# Acondicionamiento_Presion.net
KiCad netlist of a schematic drawn in Altium Designer
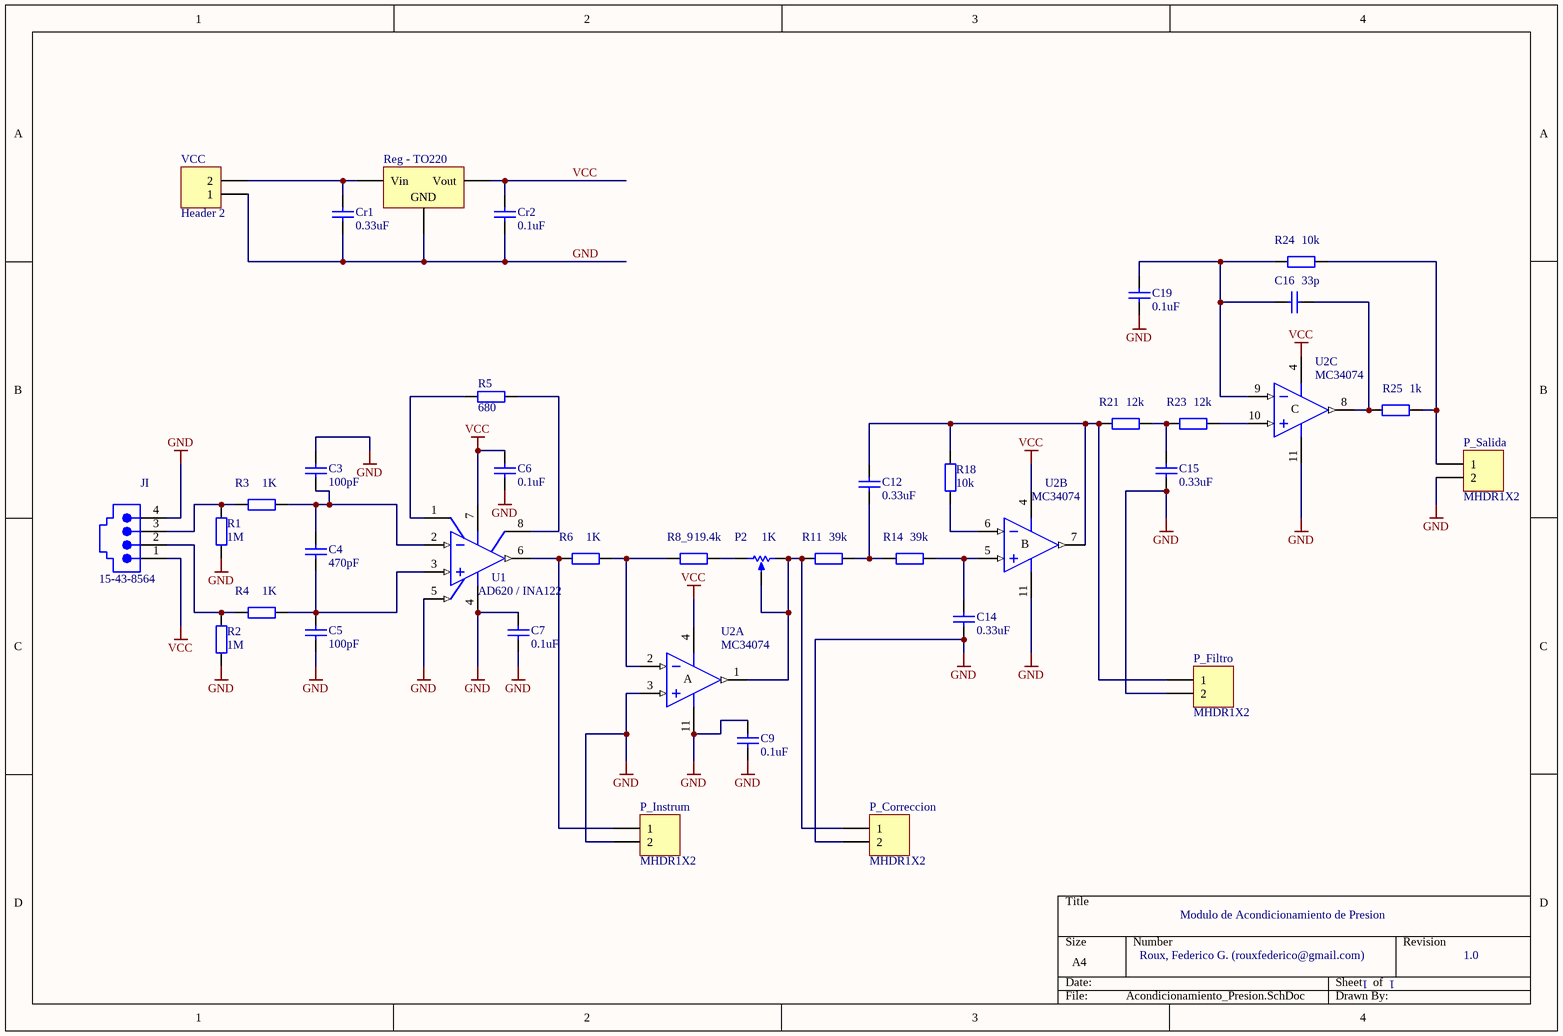
[diagram p0: Acondicionamiento_Presion.SchDoc]

(export (version "E")
  (design (tool "Eeschema 10.0.6"))
  (components
    (comp (ref "C3")
      (value "100pF")
      (footprint "AXIAL-0.3")
      (description "Capacitor")
      (fields (field (name "Comment") "Cap") (field (name "PUBLISHER") "Altium Limited"))
      (libsource (lib "Miscellaneous Devices") (part "Cap"))
    )
    (comp (ref "C4")
      (value "470pF")
      (footprint "AXIAL-0.3")
      (description "Capacitor")
      (fields (field (name "Comment") "Cap") (field (name "PUBLISHER") "Altium Limited"))
      (libsource (lib "Miscellaneous Devices") (part "Cap"))
    )
    (comp (ref "C5")
      (value "100pF")
      (footprint "AXIAL-0.3")
      (description "Capacitor")
      (fields (field (name "Comment") "Cap") (field (name "PUBLISHER") "Altium Limited"))
      (libsource (lib "Miscellaneous Devices") (part "Cap"))
    )
    (comp (ref "C6")
      (value "0.1uF")
      (footprint "AXIAL-0.3")
      (description "Capacitor")
      (fields (field (name "Comment") "Cap") (field (name "PUBLISHER") "Altium Limited"))
      (libsource (lib "Miscellaneous Devices") (part "Cap"))
    )
    (comp (ref "C7")
      (value "0.1uF")
      (footprint "AXIAL-0.3")
      (description "Capacitor")
      (fields (field (name "Comment") "Cap") (field (name "PUBLISHER") "Altium Limited"))
      (libsource (lib "Miscellaneous Devices") (part "Cap"))
    )
    (comp (ref "C9")
      (value "0.1uF")
      (footprint "AXIAL-0.3")
      (description "Capacitor")
      (fields (field (name "Comment") "Cap") (field (name "PUBLISHER") "Altium Limited"))
      (libsource (lib "Miscellaneous Devices") (part "Cap"))
    )
    (comp (ref "C12")
      (value "0.33uF")
      (footprint "AXIAL-0.3")
      (description "Capacitor")
      (fields (field (name "Comment") "Cap") (field (name "PUBLISHER") "Altium Limited"))
      (libsource (lib "Miscellaneous Devices") (part "Cap"))
    )
    (comp (ref "C14")
      (value "0.33uF")
      (footprint "AXIAL-0.3")
      (description "Capacitor")
      (fields (field (name "Comment") "Cap") (field (name "PUBLISHER") "Altium Limited"))
      (libsource (lib "Miscellaneous Devices") (part "Cap"))
    )
    (comp (ref "C15")
      (value "0.33uF")
      (footprint "AXIAL-0.3")
      (description "Capacitor")
      (fields (field (name "Comment") "Cap") (field (name "PUBLISHER") "Altium Limited"))
      (libsource (lib "Miscellaneous Devices") (part "Cap"))
    )
    (comp (ref "C16")
      (value "33p")
      (footprint "AXIAL-0.3")
      (description "Capacitor")
      (fields (field (name "Comment") "Cap") (field (name "PUBLISHER") "Altium Limited"))
      (libsource (lib "Miscellaneous Devices") (part "Cap"))
    )
    (comp (ref "C19")
      (value "0.1uF")
      (footprint "AXIAL-0.3")
      (description "Capacitor")
      (fields (field (name "Comment") "Cap") (field (name "PUBLISHER") "Altium Limited"))
      (libsource (lib "Miscellaneous Devices") (part "Cap"))
    )
    (comp (ref "Cr1")
      (value "0.33uF")
      (footprint "AXIAL-0.3")
      (description "Capacitor")
      (fields (field (name "Comment") "Cap") (field (name "PUBLISHER") "Altium Limited"))
      (libsource (lib "Miscellaneous Devices") (part "Cap"))
    )
    (comp (ref "Cr2")
      (value "0.1uF")
      (footprint "AXIAL-0.3")
      (description "Capacitor")
      (fields (field (name "Comment") "Cap") (field (name "PUBLISHER") "Altium Limited"))
      (libsource (lib "Miscellaneous Devices") (part "Cap"))
    )
    (comp (ref "JI")
      (value "15-43-8564")
      (footprint "15-43-8564")
      (description "Right Angle, Standard Profile, Unshielded PCB Jack")
      (fields (field (name "PUBLISHER") "Altium Limited"))
      (libsource (lib "Molex Modular Jack Right Angle") (part "15-43-8564"))
    )
    (comp (ref "P2")
      (value "1K")
      (footprint "VR5")
      (description "Potentiometer")
      (fields (field (name "Comment") "RPot") (field (name "PUBLISHER") "Altium Limited"))
      (libsource (lib "Miscellaneous Devices") (part "RPot"))
    )
    (comp (ref "P_Correccion")
      (value "MHDR1X2")
      (footprint "MHDR1X2")
      (description "Header, 2-Pin")
      (fields (field (name "PUBLISHER") "Altium Limited"))
      (libsource (lib "Miscellaneous Connectors") (part "MHDR1X2"))
    )
    (comp (ref "P_Filtro")
      (value "MHDR1X2")
      (footprint "MHDR1X2")
      (description "Header, 2-Pin")
      (fields (field (name "PUBLISHER") "Altium Limited"))
      (libsource (lib "Miscellaneous Connectors") (part "MHDR1X2"))
    )
    (comp (ref "P_Instrum")
      (value "MHDR1X2")
      (footprint "MHDR1X2")
      (description "Header, 2-Pin")
      (fields (field (name "PUBLISHER") "Altium Limited"))
      (libsource (lib "Miscellaneous Connectors") (part "MHDR1X2"))
    )
    (comp (ref "P_Salida")
      (value "MHDR1X2")
      (footprint "MHDR1X2")
      (description "Header, 2-Pin")
      (fields (field (name "PUBLISHER") "Altium Limited"))
      (libsource (lib "Miscellaneous Connectors") (part "MHDR1X2"))
    )
    (comp (ref "R1")
      (value "1M")
      (footprint "AXIAL-0.3")
      (description "Resistor")
      (fields (field (name "Comment") "Res2") (field (name "PUBLISHER") "Altium Limited"))
      (libsource (lib "") (part "Res2_2"))
    )
    (comp (ref "R2")
      (value "1M")
      (footprint "AXIAL-0.3")
      (description "Resistor")
      (fields (field (name "Comment") "Res2") (field (name "PUBLISHER") "Altium Limited"))
      (libsource (lib "") (part "Res2_2"))
    )
    (comp (ref "R3")
      (value "1K")
      (footprint "AXIAL-0.3")
      (description "Resistor")
      (fields (field (name "Comment") "Res2") (field (name "PUBLISHER") "Altium Limited"))
      (libsource (lib "") (part "Res2_1"))
    )
    (comp (ref "R4")
      (value "1K")
      (footprint "AXIAL-0.3")
      (description "Resistor")
      (fields (field (name "Comment") "Res2") (field (name "PUBLISHER") "Altium Limited"))
      (libsource (lib "") (part "Res2_1"))
    )
    (comp (ref "R5")
      (value "680")
      (footprint "AXIAL-0.3")
      (description "Resistor")
      (fields (field (name "Comment") "Res2") (field (name "PUBLISHER") "Altium Limited"))
      (libsource (lib "Miscellaneous Devices") (part "Res2"))
    )
    (comp (ref "R6")
      (value "1K")
      (footprint "AXIAL-0.3")
      (description "Resistor")
      (fields (field (name "Comment") "Res2") (field (name "PUBLISHER") "Altium Limited"))
      (libsource (lib "") (part "Res2_1"))
    )
    (comp (ref "R8_9")
      (value "19.4k")
      (footprint "AXIAL-0.3")
      (description "Resistor")
      (fields (field (name "Comment") "Res2") (field (name "PUBLISHER") "Altium Limited"))
      (libsource (lib "") (part "Res2_1"))
    )
    (comp (ref "R11")
      (value "39k")
      (footprint "AXIAL-0.3")
      (description "Resistor")
      (fields (field (name "Comment") "Res2") (field (name "PUBLISHER") "Altium Limited"))
      (libsource (lib "") (part "Res2_1"))
    )
    (comp (ref "R14")
      (value "39k")
      (footprint "AXIAL-0.3")
      (description "Resistor")
      (fields (field (name "Comment") "Res2") (field (name "PUBLISHER") "Altium Limited"))
      (libsource (lib "") (part "Res2_1"))
    )
    (comp (ref "R18")
      (value "10k")
      (footprint "AXIAL-0.3")
      (description "Resistor")
      (fields (field (name "Comment") "Res2") (field (name "PUBLISHER") "Altium Limited"))
      (libsource (lib "") (part "Res2_2"))
    )
    (comp (ref "R21")
      (value "12k")
      (footprint "AXIAL-0.3")
      (description "Resistor")
      (fields (field (name "Comment") "Res2") (field (name "PUBLISHER") "Altium Limited"))
      (libsource (lib "") (part "Res2_1"))
    )
    (comp (ref "R23")
      (value "12k")
      (footprint "AXIAL-0.3")
      (description "Resistor")
      (fields (field (name "Comment") "Res2") (field (name "PUBLISHER") "Altium Limited"))
      (libsource (lib "") (part "Res2_1"))
    )
    (comp (ref "R24")
      (value "10k")
      (footprint "AXIAL-0.3")
      (description "Resistor")
      (fields (field (name "Comment") "Res2") (field (name "PUBLISHER") "Altium Limited"))
      (libsource (lib "") (part "Res2_1"))
    )
    (comp (ref "R25")
      (value "1k")
      (footprint "AXIAL-0.3")
      (description "Resistor")
      (fields (field (name "Comment") "Res2") (field (name "PUBLISHER") "Altium Limited"))
      (libsource (lib "") (part "Res2_1"))
    )
    (comp (ref "Reg - TO220")
      (value "Volt Reg")
      (footprint "TO-220-AB")
      (description "Voltage Regulator")
      (fields (field (name "PUBLISHER") "Altium Limited"))
      (libsource (lib "Miscellaneous Devices") (part "Volt Reg"))
    )
    (comp (ref "U1")
      (value "AD620 / INA122")
      (footprint "DIP-8")
      (description "Low-Cost, Low-Power Instrumentation Amplifier")
      (fields (field (name "PUBLISHER") "Altium Limited"))
      (libsource (lib "AD Instrumentation Amplifier") (part "AD620BN"))
    )
    (comp (ref "U2")
      (value "MC34074")
      (footprint "DIP-14")
      (description "Quad Precision Low Cost High-Speed BiFET Operational Amplifier")
      (fields (field (name "PUBLISHER") "Altium Limited"))
      (libsource (lib "AD Operational Amplifier") (part "AD713BQ"))
    )
    (comp (ref "VCC")
      (value "Header 2")
      (footprint "HDR1X2")
      (description "Header, 2-Pin")
      (fields (field (name "PUBLISHER") "Altium Limited"))
      (libsource (lib "Miscellaneous Connectors") (part "Header 2"))
    )
  )
  (nets
    (net (code "1") (name "GND") (class "Default")
      (node (ref "C14") (pin "2") (pinfunction "2_2") (pintype "passive"))
      (node (ref "C15") (pin "2") (pinfunction "2_2") (pintype "passive"))
      (node (ref "C19") (pin "2") (pinfunction "2_2") (pintype "passive"))
      (node (ref "C3") (pin "2") (pinfunction "2_2") (pintype "passive"))
      (node (ref "C5") (pin "1") (pinfunction "1_1") (pintype "passive"))
      (node (ref "C6") (pin "2") (pinfunction "2_2") (pintype "passive"))
      (node (ref "C7") (pin "1") (pinfunction "1_1") (pintype "passive"))
      (node (ref "C7") (pin "2") (pinfunction "2_2") (pintype "passive"))
      (node (ref "C9") (pin "1") (pinfunction "1_1") (pintype "passive"))
      (node (ref "C9") (pin "2") (pinfunction "2_2") (pintype "passive"))
      (node (ref "Cr1") (pin "2") (pinfunction "2_2") (pintype "passive"))
      (node (ref "Cr2") (pin "2") (pinfunction "2_2") (pintype "passive"))
      (node (ref "JI") (pin "4") (pinfunction "4_4") (pintype "passive"))
      (node (ref "P_Correccion") (pin "2") (pinfunction "2_2") (pintype "passive"))
      (node (ref "P_Filtro") (pin "2") (pinfunction "2_2") (pintype "passive"))
      (node (ref "P_Instrum") (pin "2") (pinfunction "2_2") (pintype "passive"))
      (node (ref "P_Salida") (pin "2") (pinfunction "2_2") (pintype "passive"))
      (node (ref "R1") (pin "1") (pinfunction "1_1") (pintype "passive"))
      (node (ref "R2") (pin "1") (pinfunction "1_1") (pintype "passive"))
      (node (ref "Reg - TO220") (pin "2") (pinfunction "GND_2") (pintype "passive"))
      (node (ref "U1") (pin "4") (pinfunction "V-_4") (pintype "power_in"))
      (node (ref "U1") (pin "5") (pinfunction "REF_5") (pintype "input"))
      (node (ref "U2") (pin "11") (pinfunction "V-_11") (pintype "power_in"))
      (node (ref "U2") (pin "3") (pinfunction "IN+_3") (pintype "input"))
      (node (ref "VCC") (pin "1") (pinfunction "1_1") (pintype "passive"))
    )
    (net (code "2") (name "Net-(C12-Pad2)") (class "Default")
      (node (ref "C12") (pin "2") (pinfunction "2_2") (pintype "passive"))
      (node (ref "R11") (pin "2") (pinfunction "2_2") (pintype "passive"))
      (node (ref "R14") (pin "1") (pinfunction "1_1") (pintype "passive"))
    )
    (net (code "3") (name "Net-(C15-Pad1)") (class "Default")
      (node (ref "C15") (pin "1") (pinfunction "1_1") (pintype "passive"))
      (node (ref "R21") (pin "2") (pinfunction "2_2") (pintype "passive"))
      (node (ref "R23") (pin "1") (pinfunction "1_1") (pintype "passive"))
    )
    (net (code "4") (name "Net-(JI-Pad2)") (class "Default")
      (node (ref "JI") (pin "2") (pinfunction "2_2") (pintype "passive"))
      (node (ref "R2") (pin "2") (pinfunction "2_2") (pintype "passive"))
      (node (ref "R4") (pin "1") (pinfunction "1_1") (pintype "passive"))
    )
    (net (code "5") (name "Net-(JI-Pad3)") (class "Default")
      (node (ref "JI") (pin "3") (pinfunction "3_3") (pintype "passive"))
      (node (ref "R1") (pin "2") (pinfunction "2_2") (pintype "passive"))
      (node (ref "R3") (pin "1") (pinfunction "1_1") (pintype "passive"))
    )
    (net (code "6") (name "Net-(P2-BOT)") (class "Default")
      (node (ref "P2") (pin "2") (pinfunction "BOT_2") (pintype "passive"))
      (node (ref "P2") (pin "3") (pinfunction "TAP_3") (pintype "passive"))
      (node (ref "P_Correccion") (pin "1") (pinfunction "1_1") (pintype "passive"))
      (node (ref "R11") (pin "1") (pinfunction "1_1") (pintype "passive"))
      (node (ref "U2") (pin "1") (pinfunction "OUT_1") (pintype "output"))
    )
    (net (code "7") (name "Net-(P2-TOP)") (class "Default")
      (node (ref "P2") (pin "1") (pinfunction "TOP_1") (pintype "passive"))
      (node (ref "R8_9") (pin "2") (pinfunction "2_2") (pintype "passive"))
    )
    (net (code "8") (name "Net-(P_Salida-Pad1)") (class "Default")
      (node (ref "P_Salida") (pin "1") (pinfunction "1_1") (pintype "passive"))
      (node (ref "R24") (pin "2") (pinfunction "2_2") (pintype "passive"))
      (node (ref "R25") (pin "2") (pinfunction "2_2") (pintype "passive"))
    )
    (net (code "9") (name "Net-(R5-Pad1)") (class "Default")
      (node (ref "R5") (pin "1") (pinfunction "1_1") (pintype "passive"))
      (node (ref "U1") (pin "8") (pinfunction "RG_8") (pintype "passive"))
    )
    (net (code "10") (name "Net-(R5-Pad2)") (class "Default")
      (node (ref "R5") (pin "2") (pinfunction "2_2") (pintype "passive"))
      (node (ref "U1") (pin "1") (pinfunction "RG_1") (pintype "passive"))
    )
    (net (code "11") (name "Net-(Reg - TO220-Vin)") (class "Default")
      (node (ref "Cr1") (pin "1") (pinfunction "1_1") (pintype "passive"))
      (node (ref "Reg - TO220") (pin "1") (pinfunction "Vin_1") (pintype "passive"))
      (node (ref "VCC") (pin "2") (pinfunction "2_2") (pintype "passive"))
    )
    (net (code "12") (name "Net-(U1-+IN)") (class "Default")
      (node (ref "C4") (pin "1") (pinfunction "1_1") (pintype "passive"))
      (node (ref "C5") (pin "2") (pinfunction "2_2") (pintype "passive"))
      (node (ref "R4") (pin "2") (pinfunction "2_2") (pintype "passive"))
      (node (ref "U1") (pin "3") (pinfunction "+IN_3") (pintype "input"))
    )
    (net (code "13") (name "Net-(U1--IN)") (class "Default")
      (node (ref "C3") (pin "1") (pinfunction "1_1") (pintype "passive"))
      (node (ref "C4") (pin "2") (pinfunction "2_2") (pintype "passive"))
      (node (ref "R3") (pin "2") (pinfunction "2_2") (pintype "passive"))
      (node (ref "U1") (pin "2") (pinfunction "-IN_2") (pintype "input"))
    )
    (net (code "14") (name "Net-(U1-OUT)") (class "Default")
      (node (ref "P_Instrum") (pin "1") (pinfunction "1_1") (pintype "passive"))
      (node (ref "R6") (pin "1") (pinfunction "1_1") (pintype "passive"))
      (node (ref "U1") (pin "6") (pinfunction "OUT_6") (pintype "output"))
    )
    (net (code "15") (name "Net-(U2A-IN-)") (class "Default")
      (node (ref "R6") (pin "2") (pinfunction "2_2") (pintype "passive"))
      (node (ref "R8_9") (pin "1") (pinfunction "1_1") (pintype "passive"))
      (node (ref "U2") (pin "2") (pinfunction "IN-_2") (pintype "input"))
    )
    (net (code "16") (name "Net-(U2B-IN+)") (class "Default")
      (node (ref "C14") (pin "1") (pinfunction "1_1") (pintype "passive"))
      (node (ref "R14") (pin "2") (pinfunction "2_2") (pintype "passive"))
      (node (ref "U2") (pin "5") (pinfunction "IN+_5") (pintype "input"))
    )
    (net (code "17") (name "Net-(U2B-IN-)") (class "Default")
      (node (ref "R18") (pin "1") (pinfunction "1_1") (pintype "passive"))
      (node (ref "U2") (pin "6") (pinfunction "IN-_6") (pintype "input"))
    )
    (net (code "18") (name "Net-(U2B-OUT)") (class "Default")
      (node (ref "C12") (pin "1") (pinfunction "1_1") (pintype "passive"))
      (node (ref "P_Filtro") (pin "1") (pinfunction "1_1") (pintype "passive"))
      (node (ref "R18") (pin "2") (pinfunction "2_2") (pintype "passive"))
      (node (ref "R21") (pin "1") (pinfunction "1_1") (pintype "passive"))
      (node (ref "U2") (pin "7") (pinfunction "OUT_7") (pintype "output"))
    )
    (net (code "19") (name "Net-(U2C-IN+)") (class "Default")
      (node (ref "R23") (pin "2") (pinfunction "2_2") (pintype "passive"))
      (node (ref "U2") (pin "10") (pinfunction "IN+_10") (pintype "input"))
    )
    (net (code "20") (name "Net-(U2C-IN-)") (class "Default")
      (node (ref "C16") (pin "1") (pinfunction "1_1") (pintype "passive"))
      (node (ref "C19") (pin "1") (pinfunction "1_1") (pintype "passive"))
      (node (ref "R24") (pin "1") (pinfunction "1_1") (pintype "passive"))
      (node (ref "U2") (pin "9") (pinfunction "IN-_9") (pintype "input"))
    )
    (net (code "21") (name "Net-(U2C-OUT)") (class "Default")
      (node (ref "C16") (pin "2") (pinfunction "2_2") (pintype "passive"))
      (node (ref "R25") (pin "1") (pinfunction "1_1") (pintype "passive"))
      (node (ref "U2") (pin "8") (pinfunction "OUT_8") (pintype "output"))
    )
    (net (code "22") (name "VCC") (class "Default")
      (node (ref "C6") (pin "1") (pinfunction "1_1") (pintype "passive"))
      (node (ref "Cr2") (pin "1") (pinfunction "1_1") (pintype "passive"))
      (node (ref "JI") (pin "1") (pinfunction "1_1") (pintype "passive"))
      (node (ref "Reg - TO220") (pin "3") (pinfunction "Vout_3") (pintype "passive"))
      (node (ref "U1") (pin "7") (pinfunction "V+_7") (pintype "power_in"))
      (node (ref "U2") (pin "4") (pinfunction "V+_4") (pintype "power_in"))
    )
  )
)
